# Sheet2.net
KiCad netlist of a schematic drawn in Altium Designer
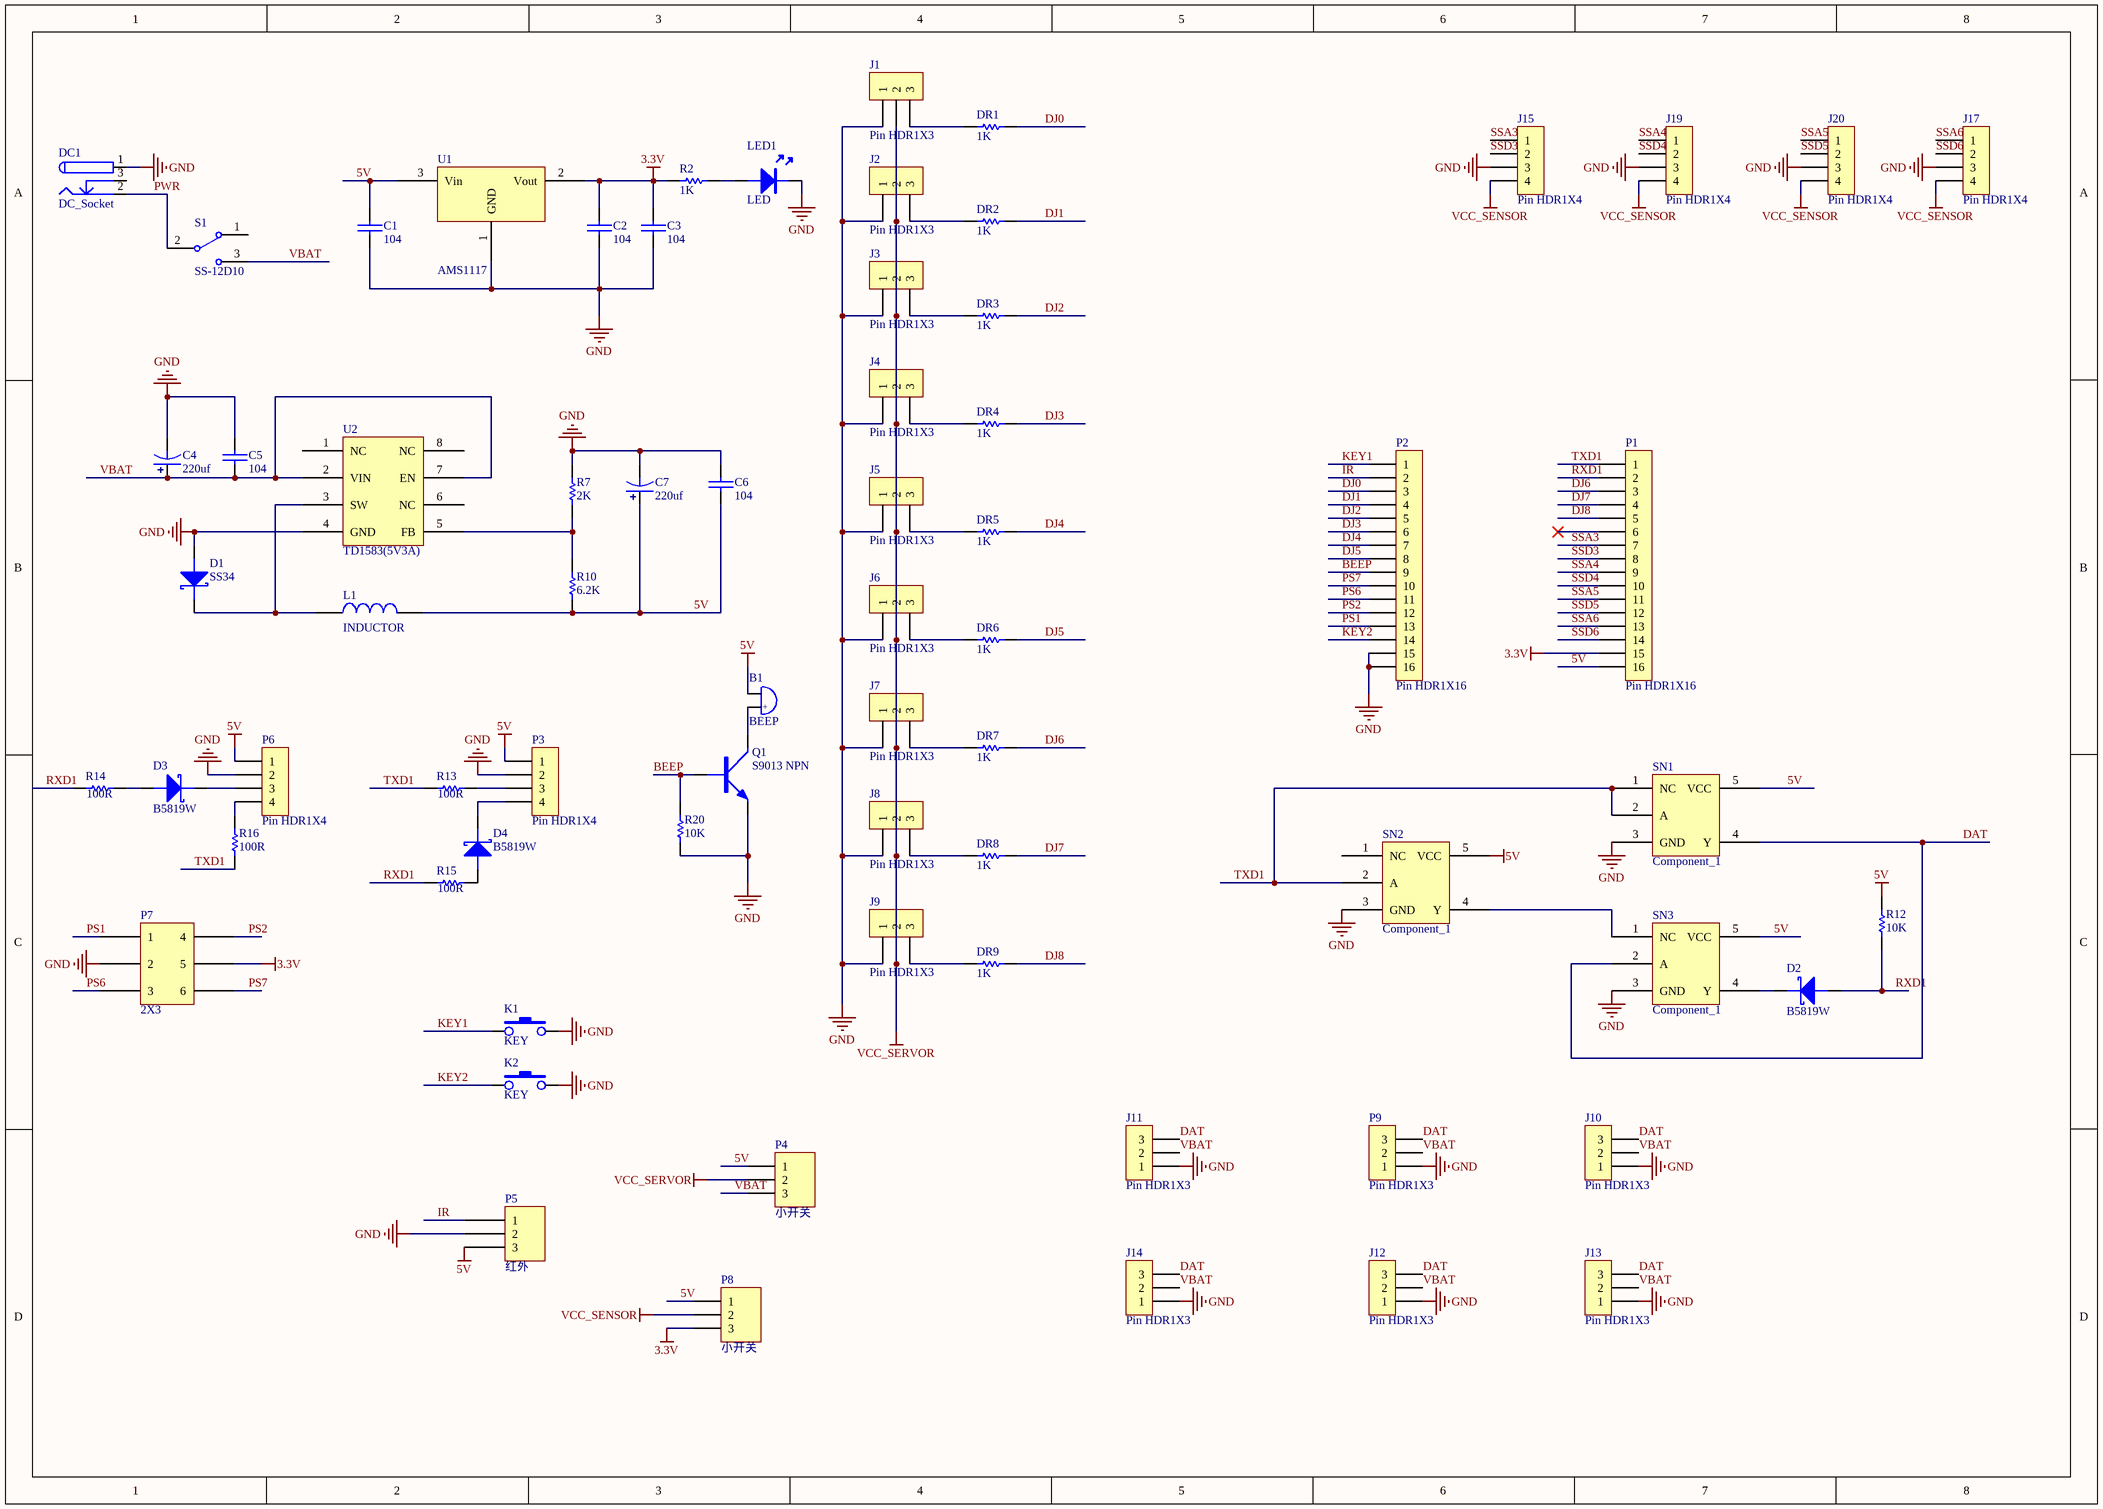
[diagram p0: Sheet2.SchDoc]

(export (version "E")
  (design (tool "Eeschema 10.0.6"))
  (components
    (comp (ref "B1")
      (value "BEEP")
      (footprint "BEEP 5x9x5.5")
      (description "蜂鸣器")
      (libsource (lib "蜂鸣器") (part "BEEP"))
    )
    (comp (ref "C1")
      (value "104")
      (footprint "0603C")
      (description "无极性电容")
      (libsource (lib "电容") (part "CAP"))
    )
    (comp (ref "C2")
      (value "104")
      (footprint "0603C")
      (description "无极性电容")
      (libsource (lib "电容") (part "CAP"))
    )
    (comp (ref "C3")
      (value "104")
      (footprint "0603C")
      (description "无极性电容")
      (libsource (lib "电容") (part "CAP"))
    )
    (comp (ref "C4")
      (value "220uf")
      (footprint "SMD-EC6.3X6.3X10")
      (description "贴片电解电容")
      (libsource (lib "电容") (part "SMD_ECAP"))
    )
    (comp (ref "C5")
      (value "104")
      (footprint "0603C")
      (description "无极性电容")
      (libsource (lib "电容") (part "CAP"))
    )
    (comp (ref "C6")
      (value "104")
      (footprint "0603C")
      (description "无极性电容")
      (libsource (lib "电容") (part "CAP"))
    )
    (comp (ref "C7")
      (value "220uf")
      (footprint "SMD-EC6.3X6.3X10")
      (description "贴片电解电容")
      (libsource (lib "电容") (part "SMD_ECAP"))
    )
    (comp (ref "D1")
      (value "SS34")
      (footprint "SMA/DO-214AC")
      (description "肖特基二极管")
      (libsource (lib "二极管") (part "DIODE SCHOTTKY"))
    )
    (comp (ref "D2")
      (value "B5819W")
      (footprint "SOD-123")
      (description "肖特基二极管")
      (libsource (lib "二极管") (part "DIODE SCHOTTKY"))
    )
    (comp (ref "D3")
      (value "B5819W")
      (footprint "SOD-123")
      (description "肖特基二极管")
      (libsource (lib "二极管") (part "DIODE SCHOTTKY"))
    )
    (comp (ref "D4")
      (value "B5819W")
      (footprint "SOD-123")
      (description "肖特基二极管")
      (libsource (lib "二极管") (part "DIODE SCHOTTKY"))
    )
    (comp (ref "DC1") (value "DC_Socket") (footprint "DC-005") (libsource (lib "电源插座") (part "DC_Socket")))
    (comp (ref "DR1") (value "1K") (footprint "0603R") (libsource (lib "电阻") (part "RES")))
    (comp (ref "DR2") (value "1K") (footprint "0603R") (libsource (lib "电阻") (part "RES")))
    (comp (ref "DR3") (value "1K") (footprint "0603R") (libsource (lib "电阻") (part "RES")))
    (comp (ref "DR4") (value "1K") (footprint "0603R") (libsource (lib "电阻") (part "RES")))
    (comp (ref "DR5") (value "1K") (footprint "0603R") (libsource (lib "电阻") (part "RES")))
    (comp (ref "DR6") (value "1K") (footprint "0603R") (libsource (lib "电阻") (part "RES")))
    (comp (ref "DR7") (value "1K") (footprint "0603R") (libsource (lib "电阻") (part "RES")))
    (comp (ref "DR8") (value "1K") (footprint "0603R") (libsource (lib "电阻") (part "RES")))
    (comp (ref "DR9") (value "1K") (footprint "0603R") (libsource (lib "电阻") (part "RES")))
    (comp (ref "J1")
      (value "Pin HDR1X3")
      (footprint "Pin HDR1X3/2.54mm-S")
      (libsource (lib "排针") (part "Pin HDR1X3"))
    )
    (comp (ref "J2")
      (value "Pin HDR1X3")
      (footprint "Pin HDR1X3/2.54mm-S")
      (libsource (lib "排针") (part "Pin HDR1X3"))
    )
    (comp (ref "J3")
      (value "Pin HDR1X3")
      (footprint "Pin HDR1X3/2.54mm-S")
      (libsource (lib "排针") (part "Pin HDR1X3"))
    )
    (comp (ref "J4")
      (value "Pin HDR1X3")
      (footprint "Pin HDR1X3/2.54mm-S")
      (libsource (lib "排针") (part "Pin HDR1X3"))
    )
    (comp (ref "J5")
      (value "Pin HDR1X3")
      (footprint "Pin HDR1X3/2.54mm-S")
      (libsource (lib "排针") (part "Pin HDR1X3"))
    )
    (comp (ref "J6")
      (value "Pin HDR1X3")
      (footprint "Pin HDR1X3/2.54mm-S")
      (libsource (lib "排针") (part "Pin HDR1X3"))
    )
    (comp (ref "J7")
      (value "Pin HDR1X3")
      (footprint "Pin HDR1X3/2.54mm-S")
      (libsource (lib "排针") (part "Pin HDR1X3"))
    )
    (comp (ref "J8")
      (value "Pin HDR1X3")
      (footprint "Pin HDR1X3/2.54mm-S")
      (libsource (lib "排针") (part "Pin HDR1X3"))
    )
    (comp (ref "J9")
      (value "Pin HDR1X3")
      (footprint "Pin HDR1X3/2.54mm-S")
      (libsource (lib "排针") (part "Pin HDR1X3"))
    )
    (comp (ref "J10")
      (value "Pin HDR1X3")
      (footprint "Pin HDR1X3/2.54mm-S")
      (libsource (lib "") (part "Pin HDR1X3_1"))
    )
    (comp (ref "J11")
      (value "Pin HDR1X3")
      (footprint "Pin HDR1X3/2.54mm-S")
      (libsource (lib "") (part "Pin HDR1X3_1"))
    )
    (comp (ref "J12")
      (value "Pin HDR1X3")
      (footprint "Pin HDR1X3/2.54mm-S")
      (libsource (lib "") (part "Pin HDR1X3_1"))
    )
    (comp (ref "J13")
      (value "Pin HDR1X3")
      (footprint "Pin HDR1X3/2.54mm-S")
      (libsource (lib "") (part "Pin HDR1X3_1"))
    )
    (comp (ref "J14")
      (value "Pin HDR1X3")
      (footprint "Pin HDR1X3/2.54mm-S")
      (libsource (lib "") (part "Pin HDR1X3_1"))
    )
    (comp (ref "J15")
      (value "Pin HDR1X4")
      (footprint "Pin HDR1X4/2.54mm-S")
      (libsource (lib "排针") (part "Pin HDR1X4"))
    )
    (comp (ref "J17")
      (value "Pin HDR1X4")
      (footprint "Pin HDR1X4/2.54mm-S")
      (libsource (lib "排针") (part "Pin HDR1X4"))
    )
    (comp (ref "J19")
      (value "Pin HDR1X4")
      (footprint "Pin HDR1X4/2.54mm-S")
      (libsource (lib "排针") (part "Pin HDR1X4"))
    )
    (comp (ref "J20")
      (value "Pin HDR1X4")
      (footprint "Pin HDR1X4/2.54mm-S")
      (libsource (lib "排针") (part "Pin HDR1X4"))
    )
    (comp (ref "K1") (value "KEY") (footprint "SMD-3X6X2.5") (libsource (lib "轻触开关") (part "KEY")))
    (comp (ref "K2") (value "KEY") (footprint "SMD-3X6X2.5") (libsource (lib "轻触开关") (part "KEY")))
    (comp (ref "L1") (value "INDUCTOR") (footprint "0630L") (libsource (lib "电感") (part "INDUCTOR")))
    (comp (ref "LED1") (value "LED") (footprint "LED-0603Y") (libsource (lib "LED") (part "LED")))
    (comp (ref "P1")
      (value "Pin HDR1X16")
      (footprint "Pin HDR1X16/2.54mm-S")
      (libsource (lib "排针") (part "Pin HDR1X16"))
    )
    (comp (ref "P2")
      (value "Pin HDR1X16")
      (footprint "Pin HDR1X16/2.54mm-S")
      (libsource (lib "排针") (part "Pin HDR1X16"))
    )
    (comp (ref "P3")
      (value "Pin HDR1X4")
      (footprint "Pin HDR1X4/2.54mm-S")
      (libsource (lib "排针") (part "Pin HDR1X4"))
    )
    (comp (ref "P4") (value "小开关") (footprint "小开关") (libsource (lib "Schlib2") (part "小开关")))
    (comp (ref "P5") (value "红外") (footprint "红外接收模块") (libsource (lib "Schlib2") (part "红外")))
    (comp (ref "P6")
      (value "Pin HDR1X4")
      (footprint "Pin HDR1X4/2.54mm-S")
      (libsource (lib "排针") (part "Pin HDR1X4"))
    )
    (comp (ref "P7") (value "2X3") (footprint "2X3P PH2.0") (libsource (lib "Schlib2") (part "2X3 PH3.0")))
    (comp (ref "P8") (value "小开关") (footprint "小开关") (libsource (lib "Schlib2") (part "小开关")))
    (comp (ref "P9")
      (value "Pin HDR1X3")
      (footprint "Pin HDR1X3/2.54mm-S")
      (libsource (lib "") (part "Pin HDR1X3_1"))
    )
    (comp (ref "Q1")
      (value "S9013 NPN")
      (footprint "SOT-23")
      (description "NPN三极管")
      (libsource (lib "三极管") (part "NPN"))
    )
    (comp (ref "R2") (value "1K") (footprint "0603R") (libsource (lib "电阻") (part "RES")))
    (comp (ref "R7") (value "2K") (footprint "0603R") (libsource (lib "电阻") (part "RES")))
    (comp (ref "R10") (value "6.2K") (footprint "0603R") (libsource (lib "电阻") (part "RES")))
    (comp (ref "R12") (value "10K") (footprint "0603R") (libsource (lib "电阻") (part "RES")))
    (comp (ref "R13") (value "100R") (footprint "0603R") (libsource (lib "电阻") (part "RES")))
    (comp (ref "R14") (value "100R") (footprint "0603R") (libsource (lib "电阻") (part "RES")))
    (comp (ref "R15") (value "100R") (footprint "0603R") (libsource (lib "电阻") (part "RES")))
    (comp (ref "R16") (value "100R") (footprint "0603R") (libsource (lib "电阻") (part "RES")))
    (comp (ref "R20") (value "10K") (footprint "0603R") (libsource (lib "电阻") (part "RES")))
    (comp (ref "S1") (value "SS-12D10") (footprint "SS-12D10") (libsource (lib "电源开关") (part "SS-12D10")))
    (comp (ref "SN1")
      (value "Component_1")
      (footprint "SN74HC")
      (libsource (lib "Schlib2") (part "Component_1"))
    )
    (comp (ref "SN2")
      (value "Component_1")
      (footprint "SN74HC")
      (libsource (lib "Schlib2") (part "Component_1"))
    )
    (comp (ref "SN3")
      (value "Component_1")
      (footprint "SN74HC")
      (libsource (lib "Schlib2") (part "Component_1"))
    )
    (comp (ref "U1")
      (value "AMS1117")
      (footprint "SOT223")
      (description "三端稳压芯片")
      (libsource (lib "电源芯片") (part "AMS1117"))
    )
    (comp (ref "U2")
      (value "TD1583(5V3A)")
      (footprint "TD1583")
      (libsource (lib "Schlib2") (part "TD1583(5V3A)"))
    )
  )
  (nets
    (net (code "1") (name "/BEEP") (class "Default")
      (node (ref "P2") (pin "9") (pinfunction "9_9") (pintype "passive"))
      (node (ref "Q1") (pin "B") (pinfunction "B_B") (pintype "passive"))
      (node (ref "R20") (pin "2") (pinfunction "2_2") (pintype "passive"))
    )
    (net (code "2") (name "/DAT") (class "Default")
      (node (ref "J10") (pin "3") (pinfunction "3_3") (pintype "passive"))
      (node (ref "J11") (pin "3") (pinfunction "3_3") (pintype "passive"))
      (node (ref "J12") (pin "3") (pinfunction "3_3") (pintype "passive"))
      (node (ref "J13") (pin "3") (pinfunction "3_3") (pintype "passive"))
      (node (ref "J14") (pin "3") (pinfunction "3_3") (pintype "passive"))
      (node (ref "P9") (pin "3") (pinfunction "3_3") (pintype "passive"))
      (node (ref "SN1") (pin "4") (pinfunction "Y_4") (pintype "passive"))
      (node (ref "SN3") (pin "2") (pinfunction "A_2") (pintype "passive"))
    )
    (net (code "3") (name "/DJ0") (class "Default")
      (node (ref "DR1") (pin "2") (pinfunction "2_2") (pintype "passive"))
      (node (ref "P2") (pin "3") (pinfunction "3_3") (pintype "passive"))
    )
    (net (code "4") (name "/DJ1") (class "Default")
      (node (ref "DR2") (pin "2") (pinfunction "2_2") (pintype "passive"))
      (node (ref "P2") (pin "4") (pinfunction "4_4") (pintype "passive"))
    )
    (net (code "5") (name "/DJ2") (class "Default")
      (node (ref "DR3") (pin "2") (pinfunction "2_2") (pintype "passive"))
      (node (ref "P2") (pin "5") (pinfunction "5_5") (pintype "passive"))
    )
    (net (code "6") (name "/DJ3") (class "Default")
      (node (ref "DR4") (pin "2") (pinfunction "2_2") (pintype "passive"))
      (node (ref "P2") (pin "6") (pinfunction "6_6") (pintype "passive"))
    )
    (net (code "7") (name "/DJ4") (class "Default")
      (node (ref "DR5") (pin "2") (pinfunction "2_2") (pintype "passive"))
      (node (ref "P2") (pin "7") (pinfunction "7_7") (pintype "passive"))
    )
    (net (code "8") (name "/DJ5") (class "Default")
      (node (ref "DR6") (pin "2") (pinfunction "2_2") (pintype "passive"))
      (node (ref "P2") (pin "8") (pinfunction "8_8") (pintype "passive"))
    )
    (net (code "9") (name "/DJ6") (class "Default")
      (node (ref "DR7") (pin "2") (pinfunction "2_2") (pintype "passive"))
      (node (ref "P1") (pin "3") (pinfunction "3_3") (pintype "passive"))
    )
    (net (code "10") (name "/DJ7") (class "Default")
      (node (ref "DR8") (pin "2") (pinfunction "2_2") (pintype "passive"))
      (node (ref "P1") (pin "4") (pinfunction "4_4") (pintype "passive"))
    )
    (net (code "11") (name "/DJ8") (class "Default")
      (node (ref "DR9") (pin "2") (pinfunction "2_2") (pintype "passive"))
      (node (ref "P1") (pin "5") (pinfunction "5_5") (pintype "passive"))
    )
    (net (code "12") (name "/IR") (class "Default")
      (node (ref "P2") (pin "2") (pinfunction "2_2") (pintype "passive"))
      (node (ref "P5") (pin "1") (pinfunction "1_1") (pintype "passive"))
    )
    (net (code "13") (name "/KEY1") (class "Default")
      (node (ref "K1") (pin "1") (pinfunction "1_1") (pintype "passive"))
      (node (ref "P2") (pin "1") (pinfunction "1_1") (pintype "passive"))
    )
    (net (code "14") (name "/KEY2") (class "Default")
      (node (ref "K2") (pin "1") (pinfunction "1_1") (pintype "passive"))
      (node (ref "P2") (pin "14") (pinfunction "14_14") (pintype "passive"))
    )
    (net (code "15") (name "/PS1") (class "Default")
      (node (ref "P2") (pin "13") (pinfunction "13_13") (pintype "passive"))
      (node (ref "P7") (pin "1") (pinfunction "1_1") (pintype "passive"))
    )
    (net (code "16") (name "/PS2") (class "Default")
      (node (ref "P2") (pin "12") (pinfunction "12_12") (pintype "passive"))
      (node (ref "P7") (pin "4") (pinfunction "4_4") (pintype "passive"))
    )
    (net (code "17") (name "/PS6") (class "Default")
      (node (ref "P2") (pin "11") (pinfunction "11_11") (pintype "passive"))
      (node (ref "P7") (pin "3") (pinfunction "3_3") (pintype "passive"))
    )
    (net (code "18") (name "/PS7") (class "Default")
      (node (ref "P2") (pin "10") (pinfunction "10_10") (pintype "passive"))
      (node (ref "P7") (pin "6") (pinfunction "6_6") (pintype "passive"))
    )
    (net (code "19") (name "/PWR") (class "Default")
      (node (ref "DC1") (pin "2") (pinfunction "2_2") (pintype "power_in"))
      (node (ref "S1") (pin "2") (pinfunction "2_2") (pintype "passive"))
    )
    (net (code "20") (name "/RXD1") (class "Default")
      (node (ref "D2") (pin "A") (pinfunction "A_A") (pintype "passive"))
      (node (ref "P1") (pin "2") (pinfunction "2_2") (pintype "passive"))
      (node (ref "R12") (pin "2") (pinfunction "2_2") (pintype "passive"))
      (node (ref "R14") (pin "2") (pinfunction "2_2") (pintype "passive"))
      (node (ref "R15") (pin "2") (pinfunction "2_2") (pintype "passive"))
    )
    (net (code "21") (name "/SSA3") (class "Default")
      (node (ref "J15") (pin "1") (pinfunction "1_1") (pintype "passive"))
      (node (ref "P1") (pin "7") (pinfunction "7_7") (pintype "passive"))
    )
    (net (code "22") (name "/SSA4") (class "Default")
      (node (ref "J19") (pin "1") (pinfunction "1_1") (pintype "passive"))
      (node (ref "P1") (pin "9") (pinfunction "9_9") (pintype "passive"))
    )
    (net (code "23") (name "/SSA5") (class "Default")
      (node (ref "J20") (pin "1") (pinfunction "1_1") (pintype "passive"))
      (node (ref "P1") (pin "11") (pinfunction "11_11") (pintype "passive"))
    )
    (net (code "24") (name "/SSA6") (class "Default")
      (node (ref "J17") (pin "1") (pinfunction "1_1") (pintype "passive"))
      (node (ref "P1") (pin "13") (pinfunction "13_13") (pintype "passive"))
    )
    (net (code "25") (name "/SSD3") (class "Default")
      (node (ref "J15") (pin "2") (pinfunction "2_2") (pintype "passive"))
      (node (ref "P1") (pin "8") (pinfunction "8_8") (pintype "passive"))
    )
    (net (code "26") (name "/SSD4") (class "Default")
      (node (ref "J19") (pin "2") (pinfunction "2_2") (pintype "passive"))
      (node (ref "P1") (pin "10") (pinfunction "10_10") (pintype "passive"))
    )
    (net (code "27") (name "/SSD5") (class "Default")
      (node (ref "J20") (pin "2") (pinfunction "2_2") (pintype "passive"))
      (node (ref "P1") (pin "12") (pinfunction "12_12") (pintype "passive"))
    )
    (net (code "28") (name "/SSD6") (class "Default")
      (node (ref "J17") (pin "2") (pinfunction "2_2") (pintype "passive"))
      (node (ref "P1") (pin "14") (pinfunction "14_14") (pintype "passive"))
    )
    (net (code "29") (name "/TXD1") (class "Default")
      (node (ref "P1") (pin "1") (pinfunction "1_1") (pintype "passive"))
      (node (ref "R13") (pin "2") (pinfunction "2_2") (pintype "passive"))
      (node (ref "R16") (pin "2") (pinfunction "2_2") (pintype "passive"))
      (node (ref "SN1") (pin "1") (pinfunction "NC_1") (pintype "passive"))
      (node (ref "SN1") (pin "2") (pinfunction "A_2") (pintype "passive"))
      (node (ref "SN2") (pin "2") (pinfunction "A_2") (pintype "passive"))
    )
    (net (code "30") (name "/VBAT") (class "Default")
      (node (ref "C4") (pin "1") (pinfunction "1_1") (pintype "passive"))
      (node (ref "C5") (pin "1") (pinfunction "1_1") (pintype "passive"))
      (node (ref "J10") (pin "2") (pinfunction "2_2") (pintype "passive"))
      (node (ref "J11") (pin "2") (pinfunction "2_2") (pintype "passive"))
      (node (ref "J12") (pin "2") (pinfunction "2_2") (pintype "passive"))
      (node (ref "J13") (pin "2") (pinfunction "2_2") (pintype "passive"))
      (node (ref "J14") (pin "2") (pinfunction "2_2") (pintype "passive"))
      (node (ref "P4") (pin "3") (pinfunction "3_3") (pintype "passive"))
      (node (ref "P9") (pin "2") (pinfunction "2_2") (pintype "passive"))
      (node (ref "S1") (pin "3") (pinfunction "3_3") (pintype "passive"))
      (node (ref "U2") (pin "2") (pinfunction "VIN_2") (pintype "passive"))
      (node (ref "U2") (pin "7") (pinfunction "EN_7") (pintype "passive"))
    )
    (net (code "31") (name "3.3V") (class "Default")
      (node (ref "C2") (pin "2") (pinfunction "2_2") (pintype "passive"))
      (node (ref "C3") (pin "2") (pinfunction "2_2") (pintype "passive"))
      (node (ref "P1") (pin "15") (pinfunction "15_15") (pintype "passive"))
      (node (ref "P7") (pin "5") (pinfunction "5_5") (pintype "passive"))
      (node (ref "P8") (pin "3") (pinfunction "3_3") (pintype "passive"))
      (node (ref "R2") (pin "1") (pinfunction "1_1") (pintype "passive"))
      (node (ref "U1") (pin "2") (pinfunction "Vout_2") (pintype "passive"))
    )
    (net (code "32") (name "5V") (class "Default")
      (node (ref "B1") (pin "2") (pinfunction "2_2") (pintype "passive"))
      (node (ref "C1") (pin "2") (pinfunction "2_2") (pintype "passive"))
      (node (ref "C6") (pin "1") (pinfunction "1_1") (pintype "passive"))
      (node (ref "C7") (pin "1") (pinfunction "1_1") (pintype "passive"))
      (node (ref "L1") (pin "2") (pinfunction "2_2") (pintype "passive"))
      (node (ref "P1") (pin "16") (pinfunction "16_16") (pintype "passive"))
      (node (ref "P3") (pin "1") (pinfunction "1_1") (pintype "passive"))
      (node (ref "P4") (pin "1") (pinfunction "1_1") (pintype "passive"))
      (node (ref "P5") (pin "3") (pinfunction "3_3") (pintype "passive"))
      (node (ref "P6") (pin "1") (pinfunction "1_1") (pintype "passive"))
      (node (ref "P8") (pin "1") (pinfunction "1_1") (pintype "passive"))
      (node (ref "R10") (pin "1") (pinfunction "1_1") (pintype "passive"))
      (node (ref "R12") (pin "1") (pinfunction "1_1") (pintype "passive"))
      (node (ref "SN1") (pin "5") (pinfunction "VCC_5") (pintype "passive"))
      (node (ref "SN2") (pin "5") (pinfunction "VCC_5") (pintype "passive"))
      (node (ref "SN3") (pin "5") (pinfunction "VCC_5") (pintype "passive"))
      (node (ref "U1") (pin "3") (pinfunction "Vin_3") (pintype "passive"))
    )
    (net (code "33") (name "GND") (class "Default")
      (node (ref "C1") (pin "1") (pinfunction "1_1") (pintype "passive"))
      (node (ref "C2") (pin "1") (pinfunction "1_1") (pintype "passive"))
      (node (ref "C3") (pin "1") (pinfunction "1_1") (pintype "passive"))
      (node (ref "C4") (pin "2") (pinfunction "2_2") (pintype "passive"))
      (node (ref "C5") (pin "2") (pinfunction "2_2") (pintype "passive"))
      (node (ref "C6") (pin "2") (pinfunction "2_2") (pintype "passive"))
      (node (ref "C7") (pin "2") (pinfunction "2_2") (pintype "passive"))
      (node (ref "D1") (pin "A") (pinfunction "A_A") (pintype "passive"))
      (node (ref "DC1") (pin "1") (pinfunction "1_1") (pintype "power_in"))
      (node (ref "J1") (pin "1") (pinfunction "1_1") (pintype "passive"))
      (node (ref "J10") (pin "1") (pinfunction "1_1") (pintype "passive"))
      (node (ref "J11") (pin "1") (pinfunction "1_1") (pintype "passive"))
      (node (ref "J12") (pin "1") (pinfunction "1_1") (pintype "passive"))
      (node (ref "J13") (pin "1") (pinfunction "1_1") (pintype "passive"))
      (node (ref "J14") (pin "1") (pinfunction "1_1") (pintype "passive"))
      (node (ref "J15") (pin "3") (pinfunction "3_3") (pintype "passive"))
      (node (ref "J17") (pin "3") (pinfunction "3_3") (pintype "passive"))
      (node (ref "J19") (pin "3") (pinfunction "3_3") (pintype "passive"))
      (node (ref "J2") (pin "1") (pinfunction "1_1") (pintype "passive"))
      (node (ref "J20") (pin "3") (pinfunction "3_3") (pintype "passive"))
      (node (ref "J3") (pin "1") (pinfunction "1_1") (pintype "passive"))
      (node (ref "J4") (pin "1") (pinfunction "1_1") (pintype "passive"))
      (node (ref "J5") (pin "1") (pinfunction "1_1") (pintype "passive"))
      (node (ref "J6") (pin "1") (pinfunction "1_1") (pintype "passive"))
      (node (ref "J7") (pin "1") (pinfunction "1_1") (pintype "passive"))
      (node (ref "J8") (pin "1") (pinfunction "1_1") (pintype "passive"))
      (node (ref "J9") (pin "1") (pinfunction "1_1") (pintype "passive"))
      (node (ref "K1") (pin "3") (pinfunction "3_3") (pintype "passive"))
      (node (ref "K2") (pin "3") (pinfunction "3_3") (pintype "passive"))
      (node (ref "LED1") (pin "K") (pinfunction "K_K") (pintype "passive"))
      (node (ref "P2") (pin "15") (pinfunction "15_15") (pintype "passive"))
      (node (ref "P2") (pin "16") (pinfunction "16_16") (pintype "passive"))
      (node (ref "P3") (pin "2") (pinfunction "2_2") (pintype "passive"))
      (node (ref "P5") (pin "2") (pinfunction "2_2") (pintype "passive"))
      (node (ref "P6") (pin "2") (pinfunction "2_2") (pintype "passive"))
      (node (ref "P7") (pin "2") (pinfunction "2_2") (pintype "passive"))
      (node (ref "P9") (pin "1") (pinfunction "1_1") (pintype "passive"))
      (node (ref "Q1") (pin "E") (pinfunction "E_E") (pintype "passive"))
      (node (ref "R20") (pin "1") (pinfunction "1_1") (pintype "passive"))
      (node (ref "R7") (pin "2") (pinfunction "2_2") (pintype "passive"))
      (node (ref "SN1") (pin "3") (pinfunction "GND_3") (pintype "passive"))
      (node (ref "SN2") (pin "3") (pinfunction "GND_3") (pintype "passive"))
      (node (ref "SN3") (pin "3") (pinfunction "GND_3") (pintype "passive"))
      (node (ref "U1") (pin "1") (pinfunction "GND_1") (pintype "passive"))
      (node (ref "U2") (pin "4") (pinfunction "GND_4") (pintype "passive"))
    )
    (net (code "34") (name "Net-(B1-Pad1)") (class "Default")
      (node (ref "B1") (pin "1") (pinfunction "1_1") (pintype "passive"))
      (node (ref "Q1") (pin "C") (pinfunction "C_C") (pintype "passive"))
    )
    (net (code "35") (name "Net-(D3-PadA)") (class "Default")
      (node (ref "D3") (pin "A") (pinfunction "A_A") (pintype "passive"))
      (node (ref "R14") (pin "1") (pinfunction "1_1") (pintype "passive"))
    )
    (net (code "36") (name "Net-(D3-PadK)") (class "Default")
      (node (ref "D3") (pin "K") (pinfunction "K_K") (pintype "passive"))
      (node (ref "P6") (pin "3") (pinfunction "3_3") (pintype "passive"))
    )
    (net (code "37") (name "Net-(D4-PadA)") (class "Default")
      (node (ref "D4") (pin "A") (pinfunction "A_A") (pintype "passive"))
      (node (ref "R15") (pin "1") (pinfunction "1_1") (pintype "passive"))
    )
    (net (code "38") (name "Net-(D4-PadK)") (class "Default")
      (node (ref "D4") (pin "K") (pinfunction "K_K") (pintype "passive"))
      (node (ref "P3") (pin "4") (pinfunction "4_4") (pintype "passive"))
    )
    (net (code "39") (name "Net-(DR1-Pad1)") (class "Default")
      (node (ref "DR1") (pin "1") (pinfunction "1_1") (pintype "passive"))
      (node (ref "J1") (pin "3") (pinfunction "3_3") (pintype "passive"))
    )
    (net (code "40") (name "Net-(DR2-Pad1)") (class "Default")
      (node (ref "DR2") (pin "1") (pinfunction "1_1") (pintype "passive"))
      (node (ref "J2") (pin "3") (pinfunction "3_3") (pintype "passive"))
    )
    (net (code "41") (name "Net-(DR3-Pad1)") (class "Default")
      (node (ref "DR3") (pin "1") (pinfunction "1_1") (pintype "passive"))
      (node (ref "J3") (pin "3") (pinfunction "3_3") (pintype "passive"))
    )
    (net (code "42") (name "Net-(DR4-Pad1)") (class "Default")
      (node (ref "DR4") (pin "1") (pinfunction "1_1") (pintype "passive"))
      (node (ref "J4") (pin "3") (pinfunction "3_3") (pintype "passive"))
    )
    (net (code "43") (name "Net-(DR5-Pad1)") (class "Default")
      (node (ref "DR5") (pin "1") (pinfunction "1_1") (pintype "passive"))
      (node (ref "J5") (pin "3") (pinfunction "3_3") (pintype "passive"))
    )
    (net (code "44") (name "Net-(DR6-Pad1)") (class "Default")
      (node (ref "DR6") (pin "1") (pinfunction "1_1") (pintype "passive"))
      (node (ref "J6") (pin "3") (pinfunction "3_3") (pintype "passive"))
    )
    (net (code "45") (name "Net-(DR7-Pad1)") (class "Default")
      (node (ref "DR7") (pin "1") (pinfunction "1_1") (pintype "passive"))
      (node (ref "J7") (pin "3") (pinfunction "3_3") (pintype "passive"))
    )
    (net (code "46") (name "Net-(DR8-Pad1)") (class "Default")
      (node (ref "DR8") (pin "1") (pinfunction "1_1") (pintype "passive"))
      (node (ref "J8") (pin "3") (pinfunction "3_3") (pintype "passive"))
    )
    (net (code "47") (name "Net-(DR9-Pad1)") (class "Default")
      (node (ref "DR9") (pin "1") (pinfunction "1_1") (pintype "passive"))
      (node (ref "J9") (pin "3") (pinfunction "3_3") (pintype "passive"))
    )
    (net (code "48") (name "Net-(LED1-PadA)") (class "Default")
      (node (ref "LED1") (pin "A") (pinfunction "A_A") (pintype "passive"))
      (node (ref "R2") (pin "2") (pinfunction "2_2") (pintype "passive"))
    )
    (net (code "49") (name "Net-(P3-Pad3)") (class "Default")
      (node (ref "P3") (pin "3") (pinfunction "3_3") (pintype "passive"))
      (node (ref "R13") (pin "1") (pinfunction "1_1") (pintype "passive"))
    )
    (net (code "50") (name "Net-(P6-Pad4)") (class "Default")
      (node (ref "P6") (pin "4") (pinfunction "4_4") (pintype "passive"))
      (node (ref "R16") (pin "1") (pinfunction "1_1") (pintype "passive"))
    )
    (net (code "51") (name "Net-(SN2-Y)") (class "Default")
      (node (ref "SN2") (pin "4") (pinfunction "Y_4") (pintype "passive"))
      (node (ref "SN3") (pin "1") (pinfunction "NC_1") (pintype "passive"))
    )
    (net (code "52") (name "Net-(SN3-Y)") (class "Default")
      (node (ref "D2") (pin "K") (pinfunction "K_K") (pintype "passive"))
      (node (ref "SN3") (pin "4") (pinfunction "Y_4") (pintype "passive"))
    )
    (net (code "53") (name "Net-(U2-FB)") (class "Default")
      (node (ref "R10") (pin "2") (pinfunction "2_2") (pintype "passive"))
      (node (ref "R7") (pin "1") (pinfunction "1_1") (pintype "passive"))
      (node (ref "U2") (pin "5") (pinfunction "FB_5") (pintype "passive"))
    )
    (net (code "54") (name "Net-(U2-SW)") (class "Default")
      (node (ref "D1") (pin "K") (pinfunction "K_K") (pintype "passive"))
      (node (ref "L1") (pin "1") (pinfunction "1_1") (pintype "passive"))
      (node (ref "U2") (pin "3") (pinfunction "SW_3") (pintype "passive"))
    )
    (net (code "55") (name "VCC_SENSOR") (class "Default")
      (node (ref "J15") (pin "4") (pinfunction "4_4") (pintype "passive"))
      (node (ref "J17") (pin "4") (pinfunction "4_4") (pintype "passive"))
      (node (ref "J19") (pin "4") (pinfunction "4_4") (pintype "passive"))
      (node (ref "J20") (pin "4") (pinfunction "4_4") (pintype "passive"))
      (node (ref "P8") (pin "2") (pinfunction "2_2") (pintype "passive"))
    )
    (net (code "56") (name "VCC_SERVOR") (class "Default")
      (node (ref "J1") (pin "2") (pinfunction "2_2") (pintype "passive"))
      (node (ref "J2") (pin "2") (pinfunction "2_2") (pintype "passive"))
      (node (ref "J3") (pin "2") (pinfunction "2_2") (pintype "passive"))
      (node (ref "J4") (pin "2") (pinfunction "2_2") (pintype "passive"))
      (node (ref "J5") (pin "2") (pinfunction "2_2") (pintype "passive"))
      (node (ref "J6") (pin "2") (pinfunction "2_2") (pintype "passive"))
      (node (ref "J7") (pin "2") (pinfunction "2_2") (pintype "passive"))
      (node (ref "J8") (pin "2") (pinfunction "2_2") (pintype "passive"))
      (node (ref "J9") (pin "2") (pinfunction "2_2") (pintype "passive"))
      (node (ref "P4") (pin "2") (pinfunction "2_2") (pintype "passive"))
    )
    (net (code "57") (name "unconnected-(DC1-Pad3)") (class "Default")
      (node (ref "DC1") (pin "3") (pinfunction "3_3") (pintype "power_in"))
    )
    (net (code "58") (name "unconnected-(P1-Pad6)") (class "Default")
      (node (ref "P1") (pin "6") (pinfunction "6_6") (pintype "passive+no_connect"))
    )
    (net (code "59") (name "unconnected-(S1-Pad1)") (class "Default")
      (node (ref "S1") (pin "1") (pinfunction "1_1") (pintype "passive"))
    )
    (net (code "60") (name "unconnected-(SN2-NC-Pad1)") (class "Default")
      (node (ref "SN2") (pin "1") (pinfunction "NC_1") (pintype "passive"))
    )
    (net (code "61") (name "unconnected-(U2-NC-Pad1)") (class "Default")
      (node (ref "U2") (pin "1") (pinfunction "NC_1") (pintype "passive"))
    )
    (net (code "62") (name "unconnected-(U2-NC-Pad6)") (class "Default")
      (node (ref "U2") (pin "6") (pinfunction "NC_6") (pintype "passive"))
    )
    (net (code "63") (name "unconnected-(U2-NC-Pad8)") (class "Default")
      (node (ref "U2") (pin "8") (pinfunction "NC_8") (pintype "passive"))
    )
  )
)
